# Ollie_JoyStick.net
KiCad netlist of a schematic drawn in Altium Designer
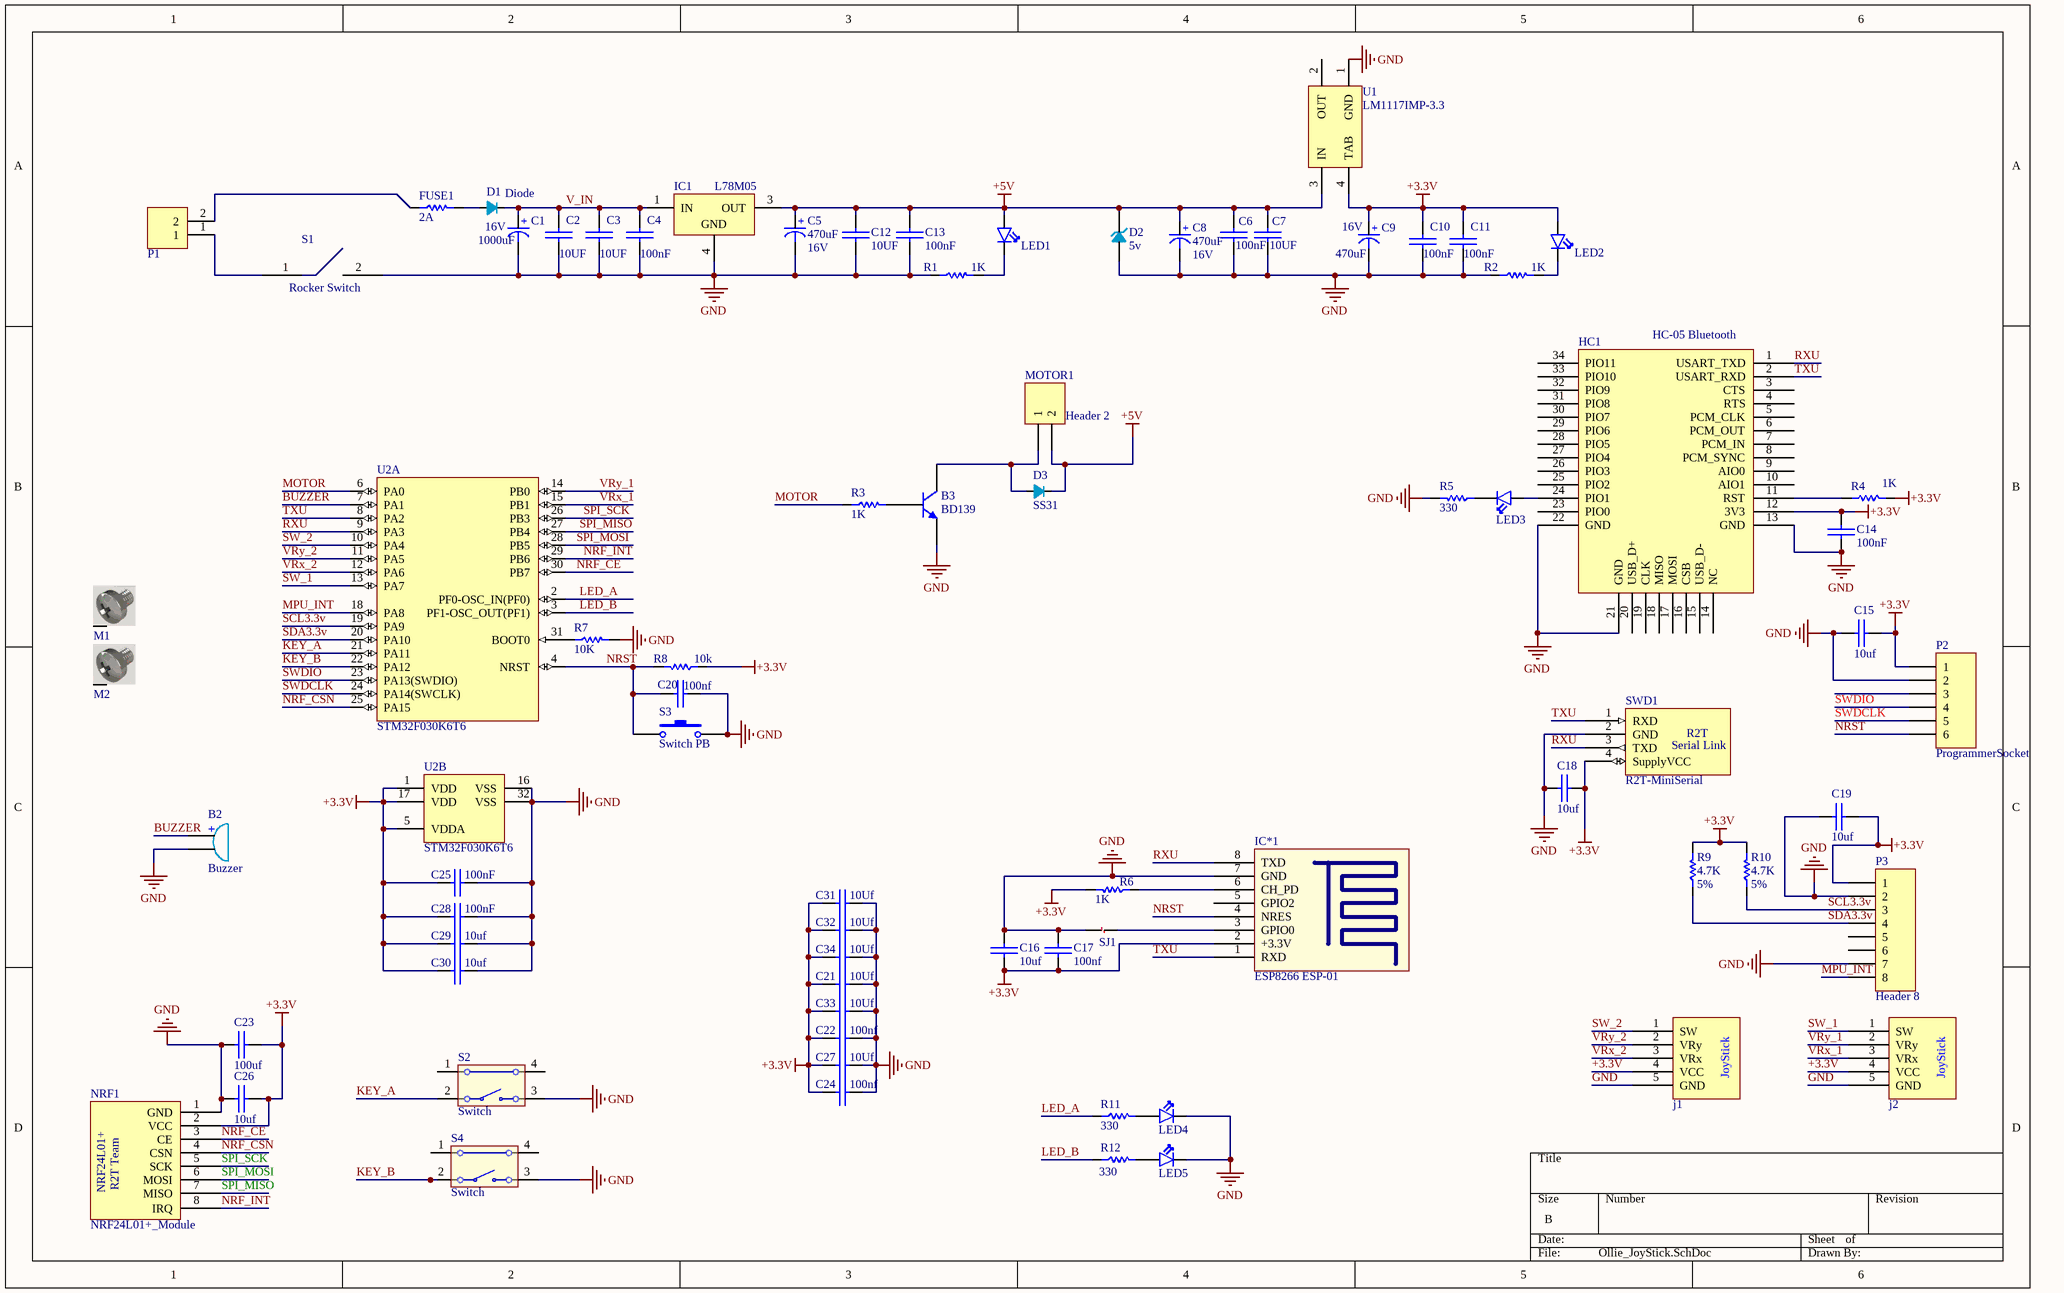
[diagram p0: Ollie_JoyStick.SchDoc]

(export (version "E")
  (design (tool "Eeschema 10.0.6"))
  (components
    (comp (ref "B2")
      (value "Buzzer")
      (footprint "Buzzer")
      (fields (field (name "DESIGNER") "Hamed Jafarzadeh"))
      (libsource (lib "R2T Team Library") (part "Buzzer"))
    )
    (comp (ref "B3")
      (value "BD139")
      (footprint "BD139")
      (description "BJT")
      (libsource (lib "My_Lib_BD139") (part "BD139"))
    )
    (comp (ref "C1")
      (value "1000uF")
      (footprint "cap 04")
      (description "Polar Capacitor")
      (fields (field (name "VOLTAGE") "16V") (field (name "DESIGNER") "Saeid Jorablo"))
      (libsource (lib "My Library") (part "Cap-Polar"))
    )
    (comp (ref "C2")
      (value "10UF")
      (footprint "SMD_CAP_1206")
      (description "Bipolar Capacitor")
      (fields (field (name "VOLTAGE") "100V") (field (name "DESIGNER") "Saeid Jorablo"))
      (libsource (lib "My Library") (part "Cap-Bipolar"))
    )
    (comp (ref "C3")
      (value "10UF")
      (footprint "SMD_CAP_1206")
      (description "Bipolar Capacitor")
      (fields (field (name "VOLTAGE") "100V") (field (name "DESIGNER") "Saeid Jorablo"))
      (libsource (lib "My Library") (part "Cap-Bipolar"))
    )
    (comp (ref "C4")
      (value "100nF")
      (footprint "SMD_CAP_1206")
      (description "Bipolar Capacitor")
      (fields (field (name "VOLTAGE") "100V") (field (name "DESIGNER") "Saeid Jorablo"))
      (libsource (lib "My Library") (part "Cap-Bipolar"))
    )
    (comp (ref "C5")
      (value "470uF")
      (footprint "cap 03")
      (description "Polar Capacitor")
      (fields (field (name "VOLTAGE") "16V") (field (name "DESIGNER") "Saeid Jorablo"))
      (libsource (lib "My Library") (part "Cap-Polar"))
    )
    (comp (ref "C6")
      (value "100nF")
      (footprint "SMD_CAP_1206")
      (description "Bipolar Capacitor")
      (fields (field (name "VOLTAGE") "100V") (field (name "DESIGNER") "Saeid Jorablo"))
      (libsource (lib "My Library") (part "Cap-Bipolar"))
    )
    (comp (ref "C7")
      (value "10UF")
      (footprint "SMD_CAP_1206")
      (description "Bipolar Capacitor")
      (fields (field (name "VOLTAGE") "100V") (field (name "DESIGNER") "Saeid Jorablo"))
      (libsource (lib "My Library") (part "Cap-Bipolar"))
    )
    (comp (ref "C8")
      (value "470uF")
      (footprint "cap 03")
      (description "Polar Capacitor")
      (fields (field (name "VOLTAGE") "16V") (field (name "DESIGNER") "Saeid Jorablo"))
      (libsource (lib "My Library") (part "Cap-Polar"))
    )
    (comp (ref "C9")
      (value "470uF")
      (footprint "cap 03")
      (description "Polar Capacitor")
      (fields (field (name "VOLTAGE") "16V") (field (name "DESIGNER") "Saeid Jorablo"))
      (libsource (lib "My Library") (part "Cap-Polar"))
    )
    (comp (ref "C10")
      (value "100nF")
      (footprint "SMD_CAP_1206")
      (description "Bipolar Capacitor")
      (fields (field (name "VOLTAGE") "100V") (field (name "DESIGNER") "Saeid Jorablo"))
      (libsource (lib "My Library") (part "Cap-Bipolar"))
    )
    (comp (ref "C11")
      (value "100nF")
      (footprint "SMD_CAP_1206")
      (description "Bipolar Capacitor")
      (fields (field (name "VOLTAGE") "100V") (field (name "DESIGNER") "Saeid Jorablo"))
      (libsource (lib "My Library") (part "Cap-Bipolar"))
    )
    (comp (ref "C12")
      (value "10UF")
      (footprint "SMD_CAP_1206")
      (description "Bipolar Capacitor")
      (fields (field (name "VOLTAGE") "100V") (field (name "DESIGNER") "Saeid Jorablo"))
      (libsource (lib "My Library") (part "Cap-Bipolar"))
    )
    (comp (ref "C13")
      (value "100nF")
      (footprint "SMD_CAP_1206")
      (description "Bipolar Capacitor")
      (fields (field (name "VOLTAGE") "100V") (field (name "DESIGNER") "Saeid Jorablo"))
      (libsource (lib "My Library") (part "Cap-Bipolar"))
    )
    (comp (ref "C14")
      (value "100nF")
      (footprint "SMD_CAP_1206")
      (description "Bipolar Capacitor")
      (fields (field (name "VOLTAGE") "100V") (field (name "DESIGNER") "Saeid Jorablo"))
      (libsource (lib "My Library") (part "Cap-Bipolar"))
    )
    (comp (ref "C15")
      (value "10uf")
      (footprint "SMD_CAP_0805")
      (description "Bipolar Capacitor")
      (fields (field (name "VOLTAGE") "100V") (field (name "DESIGNER") "Saeid Jorablo"))
      (libsource (lib "My Library") (part "Cap-Bipolar"))
    )
    (comp (ref "C16")
      (value "10uf")
      (footprint "SMD_CAP_0805")
      (description "Bipolar Capacitor")
      (fields (field (name "VOLTAGE") "100V") (field (name "DESIGNER") "Saeid Jorablo"))
      (libsource (lib "My Library") (part "Cap-Bipolar"))
    )
    (comp (ref "C17")
      (value "100nf")
      (footprint "SMD_CAP_0805")
      (description "Bipolar Capacitor")
      (fields (field (name "VOLTAGE") "100V") (field (name "DESIGNER") "Saeid Jorablo"))
      (libsource (lib "My Library") (part "Cap-Bipolar"))
    )
    (comp (ref "C18")
      (value "10uf")
      (footprint "SMD_CAP_1206")
      (description "Bipolar Capacitor")
      (fields (field (name "VOLTAGE") "100V") (field (name "DESIGNER") "Saeid Jorablo"))
      (libsource (lib "My Library") (part "Cap-Bipolar"))
    )
    (comp (ref "C19")
      (value "10uf")
      (footprint "SMD_CAP_1206")
      (description "Bipolar Capacitor")
      (fields (field (name "VOLTAGE") "100V") (field (name "DESIGNER") "Saeid Jorablo"))
      (libsource (lib "My Library") (part "Cap-Bipolar"))
    )
    (comp (ref "C20")
      (value "100nf")
      (footprint "SMD_CAP_0603")
      (description "Bipolar Capacitor")
      (fields (field (name "VOLTAGE") "100V") (field (name "DESIGNER") "Saeid Jorablo"))
      (libsource (lib "My Library") (part "Cap-Bipolar"))
    )
    (comp (ref "C21")
      (value "10Uf")
      (footprint "SMD_CAP_0805")
      (description "Bipolar Capacitor")
      (fields (field (name "VOLTAGE") "100V") (field (name "DESIGNER") "Saeid Jorablo"))
      (libsource (lib "My Library") (part "Cap-Bipolar"))
    )
    (comp (ref "C22")
      (value "100nf")
      (footprint "SMD_CAP_0805")
      (description "Bipolar Capacitor")
      (fields (field (name "VOLTAGE") "100V") (field (name "DESIGNER") "Saeid Jorablo"))
      (libsource (lib "My Library") (part "Cap-Bipolar"))
    )
    (comp (ref "C23")
      (value "100uf")
      (footprint "SMD_CAP_1206")
      (description "Bipolar Capacitor")
      (fields (field (name "VOLTAGE") "100V") (field (name "DESIGNER") "Saeid Jorablo"))
      (libsource (lib "My Library") (part "Cap-Bipolar"))
    )
    (comp (ref "C24")
      (value "100nf")
      (footprint "SMD_CAP_0805")
      (description "Bipolar Capacitor")
      (fields (field (name "VOLTAGE") "100V") (field (name "DESIGNER") "Saeid Jorablo"))
      (libsource (lib "My Library") (part "Cap-Bipolar"))
    )
    (comp (ref "C25")
      (value "100nF")
      (footprint "SMD_CAP_0805")
      (description "Bipolar Capacitor")
      (fields (field (name "VOLTAGE") "100V") (field (name "DESIGNER") "Saeid Jorablo"))
      (libsource (lib "My Library") (part "Cap-Bipolar"))
    )
    (comp (ref "C26")
      (value "10uf")
      (footprint "SMD_CAP_1206")
      (description "Bipolar Capacitor")
      (fields (field (name "VOLTAGE") "100V") (field (name "DESIGNER") "Saeid Jorablo"))
      (libsource (lib "My Library") (part "Cap-Bipolar"))
    )
    (comp (ref "C27")
      (value "10Uf")
      (footprint "SMD_CAP_0805")
      (description "Bipolar Capacitor")
      (fields (field (name "VOLTAGE") "100V") (field (name "DESIGNER") "Saeid Jorablo"))
      (libsource (lib "My Library") (part "Cap-Bipolar"))
    )
    (comp (ref "C28")
      (value "100nF")
      (footprint "SMD_CAP_0805")
      (description "Bipolar Capacitor")
      (fields (field (name "VOLTAGE") "100V") (field (name "DESIGNER") "Saeid Jorablo"))
      (libsource (lib "My Library") (part "Cap-Bipolar"))
    )
    (comp (ref "C29")
      (value "10uf")
      (footprint "SMD_CAP_0805")
      (description "Bipolar Capacitor")
      (fields (field (name "VOLTAGE") "100V") (field (name "DESIGNER") "Saeid Jorablo"))
      (libsource (lib "My Library") (part "Cap-Bipolar"))
    )
    (comp (ref "C30")
      (value "10uf")
      (footprint "SMD_CAP_0805")
      (description "Bipolar Capacitor")
      (fields (field (name "VOLTAGE") "100V") (field (name "DESIGNER") "Saeid Jorablo"))
      (libsource (lib "My Library") (part "Cap-Bipolar"))
    )
    (comp (ref "C31")
      (value "10Uf")
      (footprint "SMD_CAP_0805")
      (description "Bipolar Capacitor")
      (fields (field (name "VOLTAGE") "100V") (field (name "DESIGNER") "Saeid Jorablo"))
      (libsource (lib "My Library") (part "Cap-Bipolar"))
    )
    (comp (ref "C32")
      (value "10Uf")
      (footprint "SMD_CAP_0805")
      (description "Bipolar Capacitor")
      (fields (field (name "VOLTAGE") "100V") (field (name "DESIGNER") "Saeid Jorablo"))
      (libsource (lib "My Library") (part "Cap-Bipolar"))
    )
    (comp (ref "C33")
      (value "10Uf")
      (footprint "SMD_CAP_0805")
      (description "Bipolar Capacitor")
      (fields (field (name "VOLTAGE") "100V") (field (name "DESIGNER") "Saeid Jorablo"))
      (libsource (lib "My Library") (part "Cap-Bipolar"))
    )
    (comp (ref "C34")
      (value "10Uf")
      (footprint "SMD_CAP_0805")
      (description "Bipolar Capacitor")
      (fields (field (name "VOLTAGE") "100V") (field (name "DESIGNER") "Saeid Jorablo"))
      (libsource (lib "My Library") (part "Cap-Bipolar"))
    )
    (comp (ref "D1")
      (value "SMD Diodes")
      (footprint "DO-214AC ( SMD Diode )")
      (fields (field (name "DESCRIPTION:") "Diode") (field (name "DESIGNER :") "Hamed Jafarzadeh"))
      (libsource (lib "R2T Team Library") (part "SMD Diodes"))
    )
    (comp (ref "D2")
      (value "5v")
      (footprint "DIOMELF3615N")
      (fields (field (name "DESIGNER") "Hamed Jafarzadeh"))
      (libsource (lib "R2T Team Library") (part "Diode Zener SMD"))
    )
    (comp (ref "D3")
      (value "SMD Diodes")
      (footprint "DO-214AC ( SMD Diode )")
      (fields (field (name "DESCRIPTION:") "SS31") (field (name "DESIGNER :") "Hamed Jafarzadeh"))
      (libsource (lib "R2T Team Library") (part "SMD Diodes"))
    )
    (comp (ref "FUSE1")
      (value "2A")
      (footprint "RES 1206 (3216X08L)")
      (description "Resistor")
      (libsource (lib "My Library") (part "Resistor"))
    )
    (comp (ref "HC1")
      (value "HC-05 Bluetooth")
      (footprint "HC-05")
      (libsource (lib "R2T Team Library") (part "HC-05 Bluetooth"))
    )
    (comp (ref "IC*1")
      (value "ESP8266 ESP-01")
      (footprint "ESP8266 ESP-01")
      (libsource (lib "ESP8266") (part "ESP8266 ESP-01"))
    )
    (comp (ref "IC1")
      (value "L78M05")
      (footprint "TO-252")
      (description "Precision 500mA Regulator")
      (libsource (lib "My Library") (part "L78M05"))
    )
    (comp (ref "j1") (value "joystick") (footprint "joystick") (libsource (lib "joystick") (part "joystick")))
    (comp (ref "j2") (value "joystick") (footprint "joystick") (libsource (lib "joystick") (part "joystick")))
    (comp (ref "LED1")
      (value "LED")
      (footprint "LED0805")
      (fields (field (name "DESIGNER :") "Razi Research Team Of Mashhad - Hamed Jafarzadeh"))
      (libsource (lib "R2T Team Library") (part "LED"))
    )
    (comp (ref "LED2")
      (value "LED")
      (footprint "LED0805")
      (fields (field (name "DESIGNER :") "Razi Research Team Of Mashhad - Hamed Jafarzadeh"))
      (libsource (lib "R2T Team Library") (part "LED"))
    )
    (comp (ref "LED3")
      (value "LED")
      (footprint "LED0805")
      (fields (field (name "DESIGNER :") "Razi Research Team Of Mashhad - Hamed Jafarzadeh"))
      (libsource (lib "R2T Team Library") (part "LED"))
    )
    (comp (ref "LED4")
      (value "LED")
      (footprint "LED0805")
      (fields (field (name "DESIGNER :") "Razi Research Team Of Mashhad - Hamed Jafarzadeh"))
      (libsource (lib "R2T Team Library") (part "LED"))
    )
    (comp (ref "LED5")
      (value "LED")
      (footprint "LED0805")
      (fields (field (name "DESIGNER :") "Razi Research Team Of Mashhad - Hamed Jafarzadeh"))
      (libsource (lib "R2T Team Library") (part "LED"))
    )
    (comp (ref "M1")
      (value "Screw")
      (footprint "Board Screw")
      (description "Board Screw With Spacer")
      (libsource (lib "My Library") (part "Board Screw"))
    )
    (comp (ref "M2")
      (value "Screw")
      (footprint "Board Screw")
      (description "Board Screw With Spacer")
      (libsource (lib "My Library") (part "Board Screw"))
    )
    (comp (ref "MOTOR1")
      (value "Header 2")
      (footprint "HDR1X2")
      (description "Header, 2-Pin")
      (fields (field (name "PUBLISHER") "Altium Limited"))
      (libsource (lib "Miscellaneous Connectors") (part "Header 2"))
    )
    (comp (ref "NRF1")
      (value "NRF24L01+_Module")
      (footprint "NRF24L01+_Module-LNA+PA")
      (fields (field (name "DESIGNER:") "HamedJafarzadeh"))
      (libsource (lib "R2T Team Library") (part "NRF24L01+_Module"))
    )
    (comp (ref "P1")
      (value "Connector")
      (footprint "Polarized Header 2")
      (fields (field (name "DESIGNER:") "Hamed Jafarzadeh - www.R2T.ir"))
      (libsource (lib "R2T Team Library") (part "Connector 2Pin"))
    )
    (comp (ref "P2")
      (value "ProgrammerSocket")
      (footprint "HDR1X6")
      (description "Header, 6-Pin")
      (fields (field (name "PUBLISHER") "Altium Limited"))
      (libsource (lib "Miscellaneous Connectors") (part "Header 6"))
    )
    (comp (ref "P3")
      (value "Header 8")
      (footprint "HDR1X8")
      (description "Header, 8-Pin")
      (fields (field (name "PUBLISHER") "Altium Limited"))
      (libsource (lib "Miscellaneous Connectors") (part "Header 8"))
    )
    (comp (ref "R1")
      (value "1K")
      (footprint "RES 0805 (2012X06L)")
      (description "Resistor")
      (fields (field (name "TOLERANCE") "5%") (field (name "POWER") "1/8 W"))
      (libsource (lib "My Library") (part "Resistor"))
    )
    (comp (ref "R2")
      (value "1K")
      (footprint "RES 0805 (2012X06L)")
      (description "Resistor")
      (fields (field (name "TOLERANCE") "5%") (field (name "POWER") "1/8 W"))
      (libsource (lib "My Library") (part "Resistor"))
    )
    (comp (ref "R3")
      (value "1K")
      (footprint "RES 0805 (2012X06L)")
      (description "Resistor")
      (fields (field (name "TOLERANCE") "5%") (field (name "POWER") "1/8 W"))
      (libsource (lib "My Library") (part "Resistor"))
    )
    (comp (ref "R4")
      (value "1K")
      (footprint "RES 0805 (2012X06L)")
      (description "Resistor")
      (fields (field (name "TOLERANCE") "5%") (field (name "POWER") "1/8 W"))
      (libsource (lib "My Library") (part "Resistor"))
    )
    (comp (ref "R5")
      (value "330")
      (footprint "RES 0805 (2012X06L)")
      (description "Resistor")
      (fields (field (name "TOLERANCE") "5%") (field (name "POWER") "1/8 W"))
      (libsource (lib "My Library") (part "Resistor"))
    )
    (comp (ref "R6")
      (value "1K")
      (footprint "RES 1206 (3216X08L)")
      (description "Resistor")
      (libsource (lib "My Library") (part "Resistor"))
    )
    (comp (ref "R7")
      (value "10K")
      (footprint "RES 0805 (2012X06L)")
      (description "Resistor")
      (fields (field (name "TOLERANCE") "5%") (field (name "POWER") "1/8 W"))
      (libsource (lib "My Library") (part "Resistor"))
    )
    (comp (ref "R8")
      (value "10k")
      (footprint "RES 0603 (1608X06L)")
      (description "Resistor")
      (fields (field (name "TOLERANCE") "1%") (field (name "POWER") "1/8 W"))
      (libsource (lib "My Library") (part "Resistor"))
    )
    (comp (ref "R9")
      (value "4.7K")
      (footprint "RES 0805 (2012X06L)")
      (description "Resistor")
      (fields (field (name "TOLERANCE") "5%"))
      (libsource (lib "My Library") (part "Resistor"))
    )
    (comp (ref "R10")
      (value "4.7K")
      (footprint "RES 0805 (2012X06L)")
      (description "Resistor")
      (fields (field (name "TOLERANCE") "5%"))
      (libsource (lib "My Library") (part "Resistor"))
    )
    (comp (ref "R11")
      (value "330")
      (footprint "RES 0805 (2012X06L)")
      (description "Resistor")
      (fields (field (name "TOLERANCE") "5%") (field (name "POWER") "1/8 W"))
      (libsource (lib "My Library") (part "Resistor"))
    )
    (comp (ref "R12")
      (value "330")
      (footprint "RES 0805 (2012X06L)")
      (description "Resistor")
      (fields (field (name "TOLERANCE") "5%") (field (name "POWER") "1/8 W"))
      (libsource (lib "My Library") (part "Resistor"))
    )
    (comp (ref "S1")
      (value "Rocker Switch")
      (footprint "Rocker Switch mini")
      (libsource (lib "Rocker Switch") (part "Rocker Switch"))
    )
    (comp (ref "S2")
      (value "Switch")
      (footprint "4312560387x6")
      (description "switch right angel")
      (fields
        (field (name "PARTNO") "431256038736")
        (field (name "MANUFACTURER") "Wurth Elektronik")
        (field (name "CREATED BY") "Baojun Chen")
      )
      (libsource (lib "WS-TATU_rev15a") (part "WS-TATU, 431256038736"))
    )
    (comp (ref "S3")
      (value "Switch PB")
      (footprint "SW-PB")
      (description "Push Button Switch")
      (libsource (lib "My Library") (part "Switch PB"))
    )
    (comp (ref "S4")
      (value "Switch")
      (footprint "4312560387x6")
      (description "switch right angel")
      (fields
        (field (name "PARTNO") "431256038736")
        (field (name "MANUFACTURER") "Wurth Elektronik")
        (field (name "CREATED BY") "Baojun Chen")
      )
      (libsource (lib "WS-TATU_rev15a") (part "WS-TATU, 431256038736"))
    )
    (comp (ref "SJ1")
      (value "SmdJumper")
      (footprint "SMD Jumper")
      (libsource (lib "R2T Team Library") (part "SmdJumper"))
    )
    (comp (ref "SWD1")
      (value "R2T-MiniSerial")
      (footprint "SerialWireMini")
      (libsource (lib "R2T Team Library") (part "R2T-MiniSerial"))
    )
    (comp (ref "U1")
      (value "LM1117IMP-3.3")
      (footprint "MP04A_N")
      (description "3.3 Volt, 800mA Low-Dropout Linear Regulator")
      (fields
        (field (name "MANUFACTURER") "National Semiconductor")
        (field (name "PUBLISHER") "Altium Limited")
      )
      (libsource (lib "My Library") (part "LM1117IMP-x.x"))
    )
    (comp (ref "U2")
      (value "STM32F030K6T6")
      (footprint "STM-LQFP32_N")
      (libsource (lib "STMicroelectronics STM32 F0") (part "STM32F030K6T6"))
    )
  )
  (nets
    (net (code "1") (name "+3.3V") (class "Default")
      (node (ref "C10") (pin "1") (pinfunction "+_1") (pintype "passive"))
      (node (ref "C11") (pin "1") (pinfunction "+_1") (pintype "passive"))
      (node (ref "C14") (pin "2") (pinfunction "-_2") (pintype "passive"))
      (node (ref "C15") (pin "1") (pinfunction "+_1") (pintype "passive"))
      (node (ref "C16") (pin "1") (pinfunction "+_1") (pintype "passive"))
      (node (ref "C17") (pin "1") (pinfunction "+_1") (pintype "passive"))
      (node (ref "C18") (pin "1") (pinfunction "+_1") (pintype "passive"))
      (node (ref "C19") (pin "2") (pinfunction "-_2") (pintype "passive"))
      (node (ref "C21") (pin "2") (pinfunction "-_2") (pintype "passive"))
      (node (ref "C22") (pin "2") (pinfunction "-_2") (pintype "passive"))
      (node (ref "C23") (pin "2") (pinfunction "-_2") (pintype "passive"))
      (node (ref "C24") (pin "2") (pinfunction "-_2") (pintype "passive"))
      (node (ref "C25") (pin "2") (pinfunction "-_2") (pintype "passive"))
      (node (ref "C26") (pin "2") (pinfunction "-_2") (pintype "passive"))
      (node (ref "C27") (pin "2") (pinfunction "-_2") (pintype "passive"))
      (node (ref "C28") (pin "2") (pinfunction "-_2") (pintype "passive"))
      (node (ref "C29") (pin "1") (pinfunction "+_1") (pintype "passive"))
      (node (ref "C30") (pin "1") (pinfunction "+_1") (pintype "passive"))
      (node (ref "C31") (pin "2") (pinfunction "-_2") (pintype "passive"))
      (node (ref "C32") (pin "2") (pinfunction "-_2") (pintype "passive"))
      (node (ref "C33") (pin "2") (pinfunction "-_2") (pintype "passive"))
      (node (ref "C34") (pin "2") (pinfunction "-_2") (pintype "passive"))
      (node (ref "C9") (pin "1") (pinfunction "+_1") (pintype "passive"))
      (node (ref "HC1") (pin "12") (pinfunction "3V3_12") (pintype "passive"))
      (node (ref "IC*1") (pin "2") (pinfunction "+3.3V_2") (pintype "passive"))
      (node (ref "LED2") (pin "1") (pinfunction "A_1") (pintype "passive"))
      (node (ref "NRF1") (pin "2") (pinfunction "VCC_2") (pintype "passive"))
      (node (ref "P2") (pin "1") (pinfunction "1_1") (pintype "passive"))
      (node (ref "P3") (pin "1") (pinfunction "1_1") (pintype "passive"))
      (node (ref "R10") (pin "2") (pinfunction "2_2") (pintype "passive"))
      (node (ref "R4") (pin "1") (pinfunction "1_1") (pintype "passive"))
      (node (ref "R6") (pin "2") (pinfunction "2_2") (pintype "passive"))
      (node (ref "R8") (pin "1") (pinfunction "1_1") (pintype "passive"))
      (node (ref "R9") (pin "2") (pinfunction "2_2") (pintype "passive"))
      (node (ref "SWD1") (pin "4") (pinfunction "SupplyVCC_4") (pintype "bidirectional"))
      (node (ref "U1") (pin "4") (pinfunction "TAB_4") (pintype "power_in"))
      (node (ref "U2") (pin "1") (pinfunction "VDD_1") (pintype "power_in"))
      (node (ref "U2") (pin "17") (pinfunction "VDD_17") (pintype "power_in"))
      (node (ref "U2") (pin "5") (pinfunction "VDDA_5") (pintype "power_in"))
      (node (ref "j1") (pin "4") (pinfunction "VCC_4") (pintype "passive"))
      (node (ref "j2") (pin "4") (pinfunction "VCC_4") (pintype "passive"))
    )
    (net (code "2") (name "+5V") (class "Default")
      (node (ref "C12") (pin "1") (pinfunction "+_1") (pintype "passive"))
      (node (ref "C13") (pin "1") (pinfunction "+_1") (pintype "passive"))
      (node (ref "C5") (pin "1") (pinfunction "+_1") (pintype "passive"))
      (node (ref "C6") (pin "1") (pinfunction "+_1") (pintype "passive"))
      (node (ref "C7") (pin "1") (pinfunction "+_1") (pintype "passive"))
      (node (ref "C8") (pin "1") (pinfunction "+_1") (pintype "passive"))
      (node (ref "D2") (pin "1") (pintype "passive"))
      (node (ref "D3") (pin "1") (pintype "passive"))
      (node (ref "IC1") (pin "3") (pinfunction "OUT_3") (pintype "power_in"))
      (node (ref "LED1") (pin "1") (pinfunction "A_1") (pintype "passive"))
      (node (ref "MOTOR1") (pin "2") (pinfunction "2_2") (pintype "passive"))
      (node (ref "U1") (pin "3") (pinfunction "IN_3") (pintype "power_in"))
    )
    (net (code "3") (name "/BUZZER") (class "Default")
      (node (ref "B2") (pin "1") (pinfunction "VCC_1") (pintype "passive"))
      (node (ref "U2") (pin "7") (pinfunction "PA1_7") (pintype "bidirectional"))
    )
    (net (code "4") (name "/KEY_A") (class "Default")
      (node (ref "S2") (pin "2") (pinfunction "2_2") (pintype "passive"))
      (node (ref "U2") (pin "21") (pinfunction "PA11_21") (pintype "bidirectional"))
    )
    (net (code "5") (name "/KEY_B") (class "Default")
      (node (ref "S4") (pin "2") (pinfunction "2_2") (pintype "passive"))
      (node (ref "U2") (pin "22") (pinfunction "PA12_22") (pintype "bidirectional"))
    )
    (net (code "6") (name "/LED_A") (class "Default")
      (node (ref "R11") (pin "1") (pinfunction "1_1") (pintype "passive"))
      (node (ref "U2") (pin "2") (pinfunction "PF0-OSC_IN(PF0)_2") (pintype "bidirectional"))
    )
    (net (code "7") (name "/LED_B") (class "Default")
      (node (ref "R12") (pin "1") (pinfunction "1_1") (pintype "passive"))
      (node (ref "U2") (pin "3") (pinfunction "PF1-OSC_OUT(PF1)_3") (pintype "bidirectional"))
    )
    (net (code "8") (name "/MOTOR") (class "Default")
      (node (ref "R3") (pin "1") (pinfunction "1_1") (pintype "passive"))
      (node (ref "U2") (pin "6") (pinfunction "PA0_6") (pintype "bidirectional"))
    )
    (net (code "9") (name "/MPU_INT") (class "Default")
      (node (ref "P3") (pin "8") (pinfunction "8_8") (pintype "passive"))
      (node (ref "U2") (pin "18") (pinfunction "PA8_18") (pintype "bidirectional"))
    )
    (net (code "10") (name "/NRF_CE") (class "Default")
      (node (ref "NRF1") (pin "3") (pinfunction "CE_3") (pintype "passive"))
      (node (ref "U2") (pin "30") (pinfunction "PB7_30") (pintype "bidirectional"))
    )
    (net (code "11") (name "/NRF_CSN") (class "Default")
      (node (ref "NRF1") (pin "4") (pinfunction "CSN_4") (pintype "passive"))
      (node (ref "U2") (pin "25") (pinfunction "PA15_25") (pintype "bidirectional"))
    )
    (net (code "12") (name "/NRF_INT") (class "Default")
      (node (ref "NRF1") (pin "8") (pinfunction "IRQ_8") (pintype "passive"))
      (node (ref "U2") (pin "29") (pinfunction "PB6_29") (pintype "bidirectional"))
    )
    (net (code "13") (name "/NRST") (class "Default")
      (node (ref "C20") (pin "2") (pinfunction "-_2") (pintype "passive"))
      (node (ref "IC*1") (pin "4") (pinfunction "NRES_4") (pintype "passive"))
      (node (ref "P2") (pin "6") (pinfunction "6_6") (pintype "passive"))
      (node (ref "R8") (pin "2") (pinfunction "2_2") (pintype "passive"))
      (node (ref "S3") (pin "1") (pinfunction "1_1") (pintype "passive"))
      (node (ref "U2") (pin "4") (pinfunction "NRST_4") (pintype "bidirectional"))
    )
    (net (code "14") (name "/RXU") (class "Default")
      (node (ref "HC1") (pin "1") (pinfunction "USART_TXD_1") (pintype "passive"))
      (node (ref "IC*1") (pin "8") (pinfunction "TXD_8") (pintype "passive"))
      (node (ref "SWD1") (pin "3") (pinfunction "TXD_3") (pintype "output"))
      (node (ref "U2") (pin "9") (pinfunction "PA3_9") (pintype "bidirectional"))
    )
    (net (code "15") (name "/SCL3.3v") (class "Default")
      (node (ref "P3") (pin "3") (pinfunction "3_3") (pintype "passive"))
      (node (ref "R10") (pin "1") (pinfunction "1_1") (pintype "passive"))
      (node (ref "U2") (pin "19") (pinfunction "PA9_19") (pintype "bidirectional"))
    )
    (net (code "16") (name "/SDA3.3v") (class "Default")
      (node (ref "P3") (pin "4") (pinfunction "4_4") (pintype "passive"))
      (node (ref "R9") (pin "1") (pinfunction "1_1") (pintype "passive"))
      (node (ref "U2") (pin "20") (pinfunction "PA10_20") (pintype "bidirectional"))
    )
    (net (code "17") (name "/SPI_MISO") (class "Default")
      (node (ref "NRF1") (pin "7") (pinfunction "MISO_7") (pintype "passive"))
      (node (ref "U2") (pin "27") (pinfunction "PB4_27") (pintype "bidirectional"))
    )
    (net (code "18") (name "/SPI_MOSI") (class "Default")
      (node (ref "NRF1") (pin "6") (pinfunction "MOSI_6") (pintype "passive"))
      (node (ref "U2") (pin "28") (pinfunction "PB5_28") (pintype "bidirectional"))
    )
    (net (code "19") (name "/SPI_SCK") (class "Default")
      (node (ref "NRF1") (pin "5") (pinfunction "SCK_5") (pintype "passive"))
      (node (ref "U2") (pin "26") (pinfunction "PB3_26") (pintype "bidirectional"))
    )
    (net (code "20") (name "/SWDCLK") (class "Default")
      (node (ref "P2") (pin "5") (pinfunction "5_5") (pintype "passive"))
      (node (ref "U2") (pin "24") (pinfunction "PA14(SWCLK)_24") (pintype "bidirectional"))
    )
    (net (code "21") (name "/SWDIO") (class "Default")
      (node (ref "P2") (pin "4") (pinfunction "4_4") (pintype "passive"))
      (node (ref "U2") (pin "23") (pinfunction "PA13(SWDIO)_23") (pintype "bidirectional"))
    )
    (net (code "22") (name "/SW_1") (class "Default")
      (node (ref "U2") (pin "13") (pinfunction "PA7_13") (pintype "bidirectional"))
      (node (ref "j2") (pin "1") (pinfunction "SW_1") (pintype "passive"))
    )
    (net (code "23") (name "/SW_2") (class "Default")
      (node (ref "U2") (pin "10") (pinfunction "PA4_10") (pintype "bidirectional"))
      (node (ref "j1") (pin "1") (pinfunction "SW_1") (pintype "passive"))
    )
    (net (code "24") (name "/TXU") (class "Default")
      (node (ref "HC1") (pin "2") (pinfunction "USART_RXD_2") (pintype "passive"))
      (node (ref "IC*1") (pin "1") (pinfunction "RXD_1") (pintype "passive"))
      (node (ref "SWD1") (pin "1") (pinfunction "RXD_1") (pintype "input"))
      (node (ref "U2") (pin "8") (pinfunction "PA2_8") (pintype "bidirectional"))
    )
    (net (code "25") (name "/VRx_1") (class "Default")
      (node (ref "U2") (pin "15") (pinfunction "PB1_15") (pintype "bidirectional"))
      (node (ref "j2") (pin "3") (pinfunction "VRx_3") (pintype "passive"))
    )
    (net (code "26") (name "/VRx_2") (class "Default")
      (node (ref "U2") (pin "12") (pinfunction "PA6_12") (pintype "bidirectional"))
      (node (ref "j1") (pin "3") (pinfunction "VRx_3") (pintype "passive"))
    )
    (net (code "27") (name "/VRy_1") (class "Default")
      (node (ref "U2") (pin "14") (pinfunction "PB0_14") (pintype "bidirectional"))
      (node (ref "j2") (pin "2") (pinfunction "VRy_2") (pintype "passive"))
    )
    (net (code "28") (name "/VRy_2") (class "Default")
      (node (ref "U2") (pin "11") (pinfunction "PA5_11") (pintype "bidirectional"))
      (node (ref "j1") (pin "2") (pinfunction "VRy_2") (pintype "passive"))
    )
    (net (code "29") (name "/V_IN") (class "Default")
      (node (ref "C1") (pin "1") (pinfunction "+_1") (pintype "passive"))
      (node (ref "C2") (pin "1") (pinfunction "+_1") (pintype "passive"))
      (node (ref "C3") (pin "1") (pinfunction "+_1") (pintype "passive"))
      (node (ref "C4") (pin "1") (pinfunction "+_1") (pintype "passive"))
      (node (ref "D1") (pin "1") (pintype "passive"))
      (node (ref "IC1") (pin "1") (pinfunction "IN_1") (pintype "power_in"))
    )
    (net (code "30") (name "GND") (class "Default")
      (node (ref "B2") (pin "2") (pinfunction "GND_2") (pintype "passive"))
      (node (ref "B3") (pin "E") (pinfunction "E_E") (pintype "passive"))
      (node (ref "C1") (pin "2") (pinfunction "-_2") (pintype "passive"))
      (node (ref "C10") (pin "2") (pinfunction "-_2") (pintype "passive"))
      (node (ref "C11") (pin "2") (pinfunction "-_2") (pintype "passive"))
      (node (ref "C12") (pin "2") (pinfunction "-_2") (pintype "passive"))
      (node (ref "C13") (pin "2") (pinfunction "-_2") (pintype "passive"))
      (node (ref "C14") (pin "1") (pinfunction "+_1") (pintype "passive"))
      (node (ref "C15") (pin "2") (pinfunction "-_2") (pintype "passive"))
      (node (ref "C16") (pin "2") (pinfunction "-_2") (pintype "passive"))
      (node (ref "C17") (pin "2") (pinfunction "-_2") (pintype "passive"))
      (node (ref "C18") (pin "2") (pinfunction "-_2") (pintype "passive"))
      (node (ref "C19") (pin "1") (pinfunction "+_1") (pintype "passive"))
      (node (ref "C2") (pin "2") (pinfunction "-_2") (pintype "passive"))
      (node (ref "C20") (pin "1") (pinfunction "+_1") (pintype "passive"))
      (node (ref "C21") (pin "1") (pinfunction "+_1") (pintype "passive"))
      (node (ref "C22") (pin "1") (pinfunction "+_1") (pintype "passive"))
      (node (ref "C23") (pin "1") (pinfunction "+_1") (pintype "passive"))
      (node (ref "C24") (pin "1") (pinfunction "+_1") (pintype "passive"))
      (node (ref "C25") (pin "1") (pinfunction "+_1") (pintype "passive"))
      (node (ref "C26") (pin "1") (pinfunction "+_1") (pintype "passive"))
      (node (ref "C27") (pin "1") (pinfunction "+_1") (pintype "passive"))
      (node (ref "C28") (pin "1") (pinfunction "+_1") (pintype "passive"))
      (node (ref "C29") (pin "2") (pinfunction "-_2") (pintype "passive"))
      (node (ref "C3") (pin "2") (pinfunction "-_2") (pintype "passive"))
      (node (ref "C30") (pin "2") (pinfunction "-_2") (pintype "passive"))
      (node (ref "C31") (pin "1") (pinfunction "+_1") (pintype "passive"))
      (node (ref "C32") (pin "1") (pinfunction "+_1") (pintype "passive"))
      (node (ref "C33") (pin "1") (pinfunction "+_1") (pintype "passive"))
      (node (ref "C34") (pin "1") (pinfunction "+_1") (pintype "passive"))
      (node (ref "C4") (pin "2") (pinfunction "-_2") (pintype "passive"))
      (node (ref "C5") (pin "2") (pinfunction "-_2") (pintype "passive"))
      (node (ref "C6") (pin "2") (pinfunction "-_2") (pintype "passive"))
      (node (ref "C7") (pin "2") (pinfunction "-_2") (pintype "passive"))
      (node (ref "C8") (pin "2") (pinfunction "-_2") (pintype "passive"))
      (node (ref "C9") (pin "2") (pinfunction "-_2") (pintype "passive"))
      (node (ref "D2") (pin "2") (pintype "passive"))
      (node (ref "HC1") (pin "13") (pinfunction "GND_13") (pintype "passive"))
      (node (ref "HC1") (pin "21") (pinfunction "GND_21") (pintype "passive"))
      (node (ref "HC1") (pin "22") (pinfunction "GND_22") (pintype "passive"))
      (node (ref "IC*1") (pin "7") (pinfunction "GND_7") (pintype "passive"))
      (node (ref "IC1") (pin "4") (pinfunction "GND_4") (pintype "power_in"))
      (node (ref "LED4") (pin "2") (pinfunction "K_2") (pintype "passive"))
      (node (ref "LED5") (pin "2") (pinfunction "K_2") (pintype "passive"))
      (node (ref "NRF1") (pin "1") (pinfunction "GND_1") (pintype "passive"))
      (node (ref "P2") (pin "2") (pinfunction "2_2") (pintype "passive"))
      (node (ref "P3") (pin "2") (pinfunction "2_2") (pintype "passive"))
      (node (ref "P3") (pin "7") (pinfunction "7_7") (pintype "passive"))
      (node (ref "R1") (pin "1") (pinfunction "1_1") (pintype "passive"))
      (node (ref "R2") (pin "1") (pinfunction "1_1") (pintype "passive"))
      (node (ref "R5") (pin "2") (pinfunction "2_2") (pintype "passive"))
      (node (ref "R7") (pin "2") (pinfunction "2_2") (pintype "passive"))
      (node (ref "S1") (pin "2") (pintype "power_in"))
      (node (ref "S2") (pin "3") (pinfunction "3_3") (pintype "passive"))
      (node (ref "S3") (pin "2") (pinfunction "2_2") (pintype "passive"))
      (node (ref "S4") (pin "3") (pinfunction "3_3") (pintype "passive"))
      (node (ref "SJ1") (pin "1") (pintype "passive"))
      (node (ref "SWD1") (pin "2") (pinfunction "GND_2") (pintype "passive"))
      (node (ref "U1") (pin "1") (pinfunction "GND_1") (pintype "power_in"))
      (node (ref "U2") (pin "16") (pinfunction "VSS_16") (pintype "power_in"))
      (node (ref "U2") (pin "32") (pinfunction "VSS_32") (pintype "power_in"))
      (node (ref "j1") (pin "5") (pinfunction "GND_5") (pintype "passive"))
      (node (ref "j2") (pin "5") (pinfunction "GND_5") (pintype "passive"))
    )
    (net (code "31") (name "Net-(B3-PadB)") (class "Default")
      (node (ref "B3") (pin "B") (pinfunction "B_B") (pintype "passive"))
      (node (ref "R3") (pin "2") (pinfunction "2_2") (pintype "passive"))
    )
    (net (code "32") (name "Net-(B3-PadC)") (class "Default")
      (node (ref "B3") (pin "C") (pinfunction "C_C") (pintype "passive"))
      (node (ref "D3") (pin "0") (pintype "passive"))
      (node (ref "MOTOR1") (pin "1") (pinfunction "1_1") (pintype "passive"))
    )
    (net (code "33") (name "Net-(D1-Pad0)") (class "Default")
      (node (ref "D1") (pin "0") (pintype "passive"))
      (node (ref "FUSE1") (pin "2") (pinfunction "2_2") (pintype "passive"))
    )
    (net (code "34") (name "Net-(FUSE1-Pad1)") (class "Default")
      (node (ref "FUSE1") (pin "1") (pinfunction "1_1") (pintype "passive"))
      (node (ref "P1") (pin "2") (pinfunction "2_2") (pintype "passive"))
    )
    (net (code "35") (name "Net-(HC1-PIO1)") (class "Default")
      (node (ref "HC1") (pin "24") (pinfunction "PIO1_24") (pintype "passive"))
      (node (ref "LED3") (pin "1") (pinfunction "A_1") (pintype "passive"))
    )
    (net (code "36") (name "Net-(HC1-RST)") (class "Default")
      (node (ref "HC1") (pin "11") (pinfunction "RST_11") (pintype "passive"))
      (node (ref "R4") (pin "2") (pinfunction "2_2") (pintype "passive"))
    )
    (net (code "37") (name "Net-(IC*1-CH_PD)") (class "Default")
      (node (ref "IC*1") (pin "6") (pinfunction "CH_PD_6") (pintype "passive"))
      (node (ref "R6") (pin "1") (pinfunction "1_1") (pintype "passive"))
    )
    (net (code "38") (name "Net-(IC*1-GPIO0)") (class "Default")
      (node (ref "IC*1") (pin "3") (pinfunction "GPIO0_3") (pintype "passive"))
      (node (ref "SJ1") (pin "2") (pinfunction "2_2") (pintype "passive"))
    )
    (net (code "39") (name "Net-(LED1-K)") (class "Default")
      (node (ref "LED1") (pin "2") (pinfunction "K_2") (pintype "passive"))
      (node (ref "R1") (pin "2") (pinfunction "2_2") (pintype "passive"))
    )
    (net (code "40") (name "Net-(LED2-K)") (class "Default")
      (node (ref "LED2") (pin "2") (pinfunction "K_2") (pintype "passive"))
      (node (ref "R2") (pin "2") (pinfunction "2_2") (pintype "passive"))
    )
    (net (code "41") (name "Net-(LED3-K)") (class "Default")
      (node (ref "LED3") (pin "2") (pinfunction "K_2") (pintype "passive"))
      (node (ref "R5") (pin "1") (pinfunction "1_1") (pintype "passive"))
    )
    (net (code "42") (name "Net-(LED4-A)") (class "Default")
      (node (ref "LED4") (pin "1") (pinfunction "A_1") (pintype "passive"))
      (node (ref "R11") (pin "2") (pinfunction "2_2") (pintype "passive"))
    )
    (net (code "43") (name "Net-(LED5-A)") (class "Default")
      (node (ref "LED5") (pin "1") (pinfunction "A_1") (pintype "passive"))
      (node (ref "R12") (pin "2") (pinfunction "2_2") (pintype "passive"))
    )
    (net (code "44") (name "Net-(P1-Pad1)") (class "Default")
      (node (ref "P1") (pin "1") (pinfunction "1_1") (pintype "passive"))
      (node (ref "S1") (pin "1") (pinfunction "1_1") (pintype "power_in"))
    )
    (net (code "45") (name "Net-(U2A-BOOT0)") (class "Default")
      (node (ref "R7") (pin "1") (pinfunction "1_1") (pintype "passive"))
      (node (ref "U2") (pin "31") (pinfunction "BOOT0_31") (pintype "input"))
    )
    (net (code "46") (name "unconnected-(HC1-AIO0-Pad9)") (class "Default")
      (node (ref "HC1") (pin "9") (pinfunction "AIO0_9") (pintype "passive"))
    )
    (net (code "47") (name "unconnected-(HC1-AIO1-Pad10)") (class "Default")
      (node (ref "HC1") (pin "10") (pinfunction "AIO1_10") (pintype "passive"))
    )
    (net (code "48") (name "unconnected-(HC1-CLK-Pad19)") (class "Default")
      (node (ref "HC1") (pin "19") (pinfunction "CLK_19") (pintype "passive"))
    )
    (net (code "49") (name "unconnected-(HC1-CSB-Pad16)") (class "Default")
      (node (ref "HC1") (pin "16") (pinfunction "CSB_16") (pintype "passive"))
    )
    (net (code "50") (name "unconnected-(HC1-CTS-Pad3)") (class "Default")
      (node (ref "HC1") (pin "3") (pinfunction "CTS_3") (pintype "passive"))
    )
    (net (code "51") (name "unconnected-(HC1-MISO-Pad18)") (class "Default")
      (node (ref "HC1") (pin "18") (pinfunction "MISO_18") (pintype "passive"))
    )
    (net (code "52") (name "unconnected-(HC1-MOSI-Pad17)") (class "Default")
      (node (ref "HC1") (pin "17") (pinfunction "MOSI_17") (pintype "passive"))
    )
    (net (code "53") (name "unconnected-(HC1-NC-Pad14)") (class "Default")
      (node (ref "HC1") (pin "14") (pinfunction "NC_14") (pintype "passive"))
    )
    (net (code "54") (name "unconnected-(HC1-PCM_CLK-Pad5)") (class "Default")
      (node (ref "HC1") (pin "5") (pinfunction "PCM_CLK_5") (pintype "passive"))
    )
    (net (code "55") (name "unconnected-(HC1-PCM_IN-Pad7)") (class "Default")
      (node (ref "HC1") (pin "7") (pinfunction "PCM_IN_7") (pintype "passive"))
    )
    (net (code "56") (name "unconnected-(HC1-PCM_OUT-Pad6)") (class "Default")
      (node (ref "HC1") (pin "6") (pinfunction "PCM_OUT_6") (pintype "passive"))
    )
    (net (code "57") (name "unconnected-(HC1-PCM_SYNC-Pad8)") (class "Default")
      (node (ref "HC1") (pin "8") (pinfunction "PCM_SYNC_8") (pintype "passive"))
    )
    (net (code "58") (name "unconnected-(HC1-PIO0-Pad23)") (class "Default")
      (node (ref "HC1") (pin "23") (pinfunction "PIO0_23") (pintype "passive"))
    )
    (net (code "59") (name "unconnected-(HC1-PIO2-Pad25)") (class "Default")
      (node (ref "HC1") (pin "25") (pinfunction "PIO2_25") (pintype "passive"))
    )
    (net (code "60") (name "unconnected-(HC1-PIO3-Pad26)") (class "Default")
      (node (ref "HC1") (pin "26") (pinfunction "PIO3_26") (pintype "passive"))
    )
    (net (code "61") (name "unconnected-(HC1-PIO4-Pad27)") (class "Default")
      (node (ref "HC1") (pin "27") (pinfunction "PIO4_27") (pintype "passive"))
    )
    (net (code "62") (name "unconnected-(HC1-PIO5-Pad28)") (class "Default")
      (node (ref "HC1") (pin "28") (pinfunction "PIO5_28") (pintype "passive"))
    )
    (net (code "63") (name "unconnected-(HC1-PIO6-Pad29)") (class "Default")
      (node (ref "HC1") (pin "29") (pinfunction "PIO6_29") (pintype "passive"))
    )
    (net (code "64") (name "unconnected-(HC1-PIO7-Pad30)") (class "Default")
      (node (ref "HC1") (pin "30") (pinfunction "PIO7_30") (pintype "passive"))
    )
    (net (code "65") (name "unconnected-(HC1-PIO8-Pad31)") (class "Default")
      (node (ref "HC1") (pin "31") (pinfunction "PIO8_31") (pintype "passive"))
    )
    (net (code "66") (name "unconnected-(HC1-PIO9-Pad32)") (class "Default")
      (node (ref "HC1") (pin "32") (pinfunction "PIO9_32") (pintype "passive"))
    )
    (net (code "67") (name "unconnected-(HC1-PIO10-Pad33)") (class "Default")
      (node (ref "HC1") (pin "33") (pinfunction "PIO10_33") (pintype "passive"))
    )
    (net (code "68") (name "unconnected-(HC1-PIO11-Pad34)") (class "Default")
      (node (ref "HC1") (pin "34") (pinfunction "PIO11_34") (pintype "passive"))
    )
    (net (code "69") (name "unconnected-(HC1-RTS-Pad4)") (class "Default")
      (node (ref "HC1") (pin "4") (pinfunction "RTS_4") (pintype "passive"))
    )
    (net (code "70") (name "unconnected-(HC1-USB_D+-Pad20)") (class "Default")
      (node (ref "HC1") (pin "20") (pinfunction "USB_D+_20") (pintype "passive"))
    )
    (net (code "71") (name "unconnected-(HC1-USB_D--Pad15)") (class "Default")
      (node (ref "HC1") (pin "15") (pinfunction "USB_D-_15") (pintype "passive"))
    )
    (net (code "72") (name "unconnected-(IC*1-GPIO2-Pad5)") (class "Default")
      (node (ref "IC*1") (pin "5") (pinfunction "GPIO2_5") (pintype "passive"))
    )
    (net (code "73") (name "unconnected-(M1-PadS)") (class "Default")
      (node (ref "M1") (pin "S") (pinfunction "S_S") (pintype "passive"))
    )
    (net (code "74") (name "unconnected-(M2-PadS)") (class "Default")
      (node (ref "M2") (pin "S") (pinfunction "S_S") (pintype "passive"))
    )
    (net (code "75") (name "unconnected-(P2-Pad3)") (class "Default")
      (node (ref "P2") (pin "3") (pinfunction "3_3") (pintype "passive"))
    )
    (net (code "76") (name "unconnected-(P3-Pad5)") (class "Default")
      (node (ref "P3") (pin "5") (pinfunction "5_5") (pintype "passive"))
    )
    (net (code "77") (name "unconnected-(P3-Pad6)") (class "Default")
      (node (ref "P3") (pin "6") (pinfunction "6_6") (pintype "passive"))
    )
    (net (code "78") (name "unconnected-(S2-Pad1)") (class "Default")
      (node (ref "S2") (pin "1") (pinfunction "1_1") (pintype "passive"))
    )
    (net (code "79") (name "unconnected-(S2-Pad4)") (class "Default")
      (node (ref "S2") (pin "4") (pinfunction "4_4") (pintype "passive"))
    )
    (net (code "80") (name "unconnected-(S4-Pad1)") (class "Default")
      (node (ref "S4") (pin "1") (pinfunction "1_1") (pintype "passive"))
    )
    (net (code "81") (name "unconnected-(S4-Pad4)") (class "Default")
      (node (ref "S4") (pin "4") (pinfunction "4_4") (pintype "passive"))
    )
    (net (code "82") (name "unconnected-(U1-OUT-Pad2)") (class "Default")
      (node (ref "U1") (pin "2") (pinfunction "OUT_2") (pintype "power_in"))
    )
  )
)
